# Sheet1.net
KiCad netlist of a schematic drawn in Altium Designer
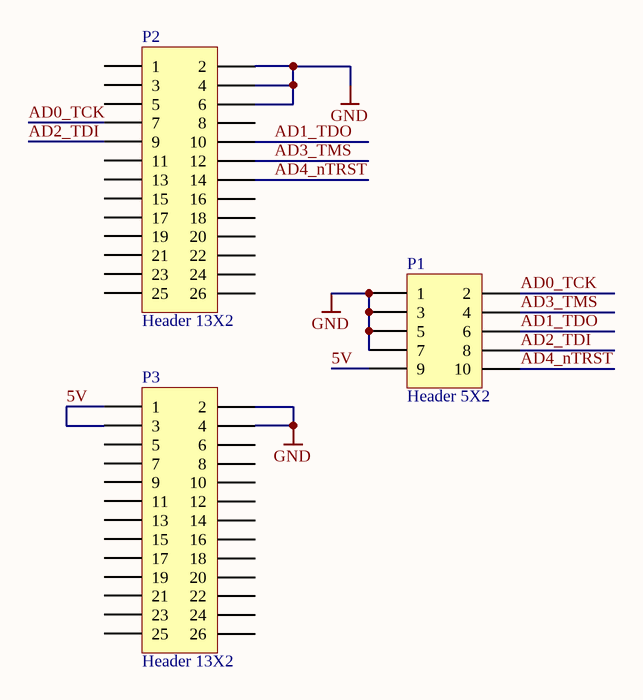
[diagram p0: Sheet1.SchDoc]

(export (version "E")
  (design (tool "Eeschema 10.0.6"))
  (components
    (comp (ref "P1")
      (value "Header 5X2")
      (footprint "HDR2X5")
      (description "Header, 5-Pin, Dual row")
      (fields (field (name "PUBLISHER") "Altium Limited"))
      (libsource (lib "Miscellaneous Connectors") (part "Header 5X2"))
    )
    (comp (ref "P2")
      (value "Header 13X2")
      (footprint "HDR2X13")
      (description "Header, 13-Pin, Dual row")
      (fields (field (name "PUBLISHER") "Altium Limited"))
      (libsource (lib "Miscellaneous Connectors") (part "Header 13X2"))
    )
    (comp (ref "P3")
      (value "Header 13X2")
      (footprint "HDR2X13")
      (description "Header, 13-Pin, Dual row")
      (fields (field (name "PUBLISHER") "Altium Limited"))
      (libsource (lib "Miscellaneous Connectors") (part "Header 13X2"))
    )
  )
  (nets
    (net (code "1") (name "/5V") (class "Default")
      (node (ref "P1") (pin "9") (pinfunction "9_9") (pintype "passive"))
      (node (ref "P3") (pin "1") (pinfunction "1_1") (pintype "passive"))
      (node (ref "P3") (pin "3") (pinfunction "3_3") (pintype "passive"))
    )
    (net (code "2") (name "/AD0_TCK") (class "Default")
      (node (ref "P1") (pin "2") (pinfunction "2_2") (pintype "passive"))
      (node (ref "P2") (pin "7") (pinfunction "7_7") (pintype "passive"))
    )
    (net (code "3") (name "/AD1_TDO") (class "Default")
      (node (ref "P1") (pin "6") (pinfunction "6_6") (pintype "passive"))
      (node (ref "P2") (pin "10") (pinfunction "10_10") (pintype "passive"))
    )
    (net (code "4") (name "/AD2_TDI") (class "Default")
      (node (ref "P1") (pin "8") (pinfunction "8_8") (pintype "passive"))
      (node (ref "P2") (pin "9") (pinfunction "9_9") (pintype "passive"))
    )
    (net (code "5") (name "/AD3_TMS") (class "Default")
      (node (ref "P1") (pin "4") (pinfunction "4_4") (pintype "passive"))
      (node (ref "P2") (pin "12") (pinfunction "12_12") (pintype "passive"))
    )
    (net (code "6") (name "/AD4_nTRST") (class "Default")
      (node (ref "P1") (pin "10") (pinfunction "10_10") (pintype "passive"))
      (node (ref "P2") (pin "14") (pinfunction "14_14") (pintype "passive"))
    )
    (net (code "7") (name "GND") (class "Default")
      (node (ref "P1") (pin "1") (pinfunction "1_1") (pintype "passive"))
      (node (ref "P1") (pin "3") (pinfunction "3_3") (pintype "passive"))
      (node (ref "P1") (pin "5") (pinfunction "5_5") (pintype "passive"))
      (node (ref "P1") (pin "7") (pinfunction "7_7") (pintype "passive"))
      (node (ref "P2") (pin "2") (pinfunction "2_2") (pintype "passive"))
      (node (ref "P2") (pin "4") (pinfunction "4_4") (pintype "passive"))
      (node (ref "P2") (pin "6") (pinfunction "6_6") (pintype "passive"))
      (node (ref "P3") (pin "2") (pinfunction "2_2") (pintype "passive"))
      (node (ref "P3") (pin "4") (pinfunction "4_4") (pintype "passive"))
    )
    (net (code "8") (name "unconnected-(P2-Pad1)") (class "Default")
      (node (ref "P2") (pin "1") (pinfunction "1_1") (pintype "passive"))
    )
    (net (code "9") (name "unconnected-(P2-Pad3)") (class "Default")
      (node (ref "P2") (pin "3") (pinfunction "3_3") (pintype "passive"))
    )
    (net (code "10") (name "unconnected-(P2-Pad5)") (class "Default")
      (node (ref "P2") (pin "5") (pinfunction "5_5") (pintype "passive"))
    )
    (net (code "11") (name "unconnected-(P2-Pad8)") (class "Default")
      (node (ref "P2") (pin "8") (pinfunction "8_8") (pintype "passive"))
    )
    (net (code "12") (name "unconnected-(P2-Pad11)") (class "Default")
      (node (ref "P2") (pin "11") (pinfunction "11_11") (pintype "passive"))
    )
    (net (code "13") (name "unconnected-(P2-Pad13)") (class "Default")
      (node (ref "P2") (pin "13") (pinfunction "13_13") (pintype "passive"))
    )
    (net (code "14") (name "unconnected-(P2-Pad15)") (class "Default")
      (node (ref "P2") (pin "15") (pinfunction "15_15") (pintype "passive"))
    )
    (net (code "15") (name "unconnected-(P2-Pad16)") (class "Default")
      (node (ref "P2") (pin "16") (pinfunction "16_16") (pintype "passive"))
    )
    (net (code "16") (name "unconnected-(P2-Pad17)") (class "Default")
      (node (ref "P2") (pin "17") (pinfunction "17_17") (pintype "passive"))
    )
    (net (code "17") (name "unconnected-(P2-Pad18)") (class "Default")
      (node (ref "P2") (pin "18") (pinfunction "18_18") (pintype "passive"))
    )
    (net (code "18") (name "unconnected-(P2-Pad19)") (class "Default")
      (node (ref "P2") (pin "19") (pinfunction "19_19") (pintype "passive"))
    )
    (net (code "19") (name "unconnected-(P2-Pad20)") (class "Default")
      (node (ref "P2") (pin "20") (pinfunction "20_20") (pintype "passive"))
    )
    (net (code "20") (name "unconnected-(P2-Pad21)") (class "Default")
      (node (ref "P2") (pin "21") (pinfunction "21_21") (pintype "passive"))
    )
    (net (code "21") (name "unconnected-(P2-Pad22)") (class "Default")
      (node (ref "P2") (pin "22") (pinfunction "22_22") (pintype "passive"))
    )
    (net (code "22") (name "unconnected-(P2-Pad23)") (class "Default")
      (node (ref "P2") (pin "23") (pinfunction "23_23") (pintype "passive"))
    )
    (net (code "23") (name "unconnected-(P2-Pad24)") (class "Default")
      (node (ref "P2") (pin "24") (pinfunction "24_24") (pintype "passive"))
    )
    (net (code "24") (name "unconnected-(P2-Pad25)") (class "Default")
      (node (ref "P2") (pin "25") (pinfunction "25_25") (pintype "passive"))
    )
    (net (code "25") (name "unconnected-(P2-Pad26)") (class "Default")
      (node (ref "P2") (pin "26") (pinfunction "26_26") (pintype "passive"))
    )
    (net (code "26") (name "unconnected-(P3-Pad5)") (class "Default")
      (node (ref "P3") (pin "5") (pinfunction "5_5") (pintype "passive"))
    )
    (net (code "27") (name "unconnected-(P3-Pad6)") (class "Default")
      (node (ref "P3") (pin "6") (pinfunction "6_6") (pintype "passive"))
    )
    (net (code "28") (name "unconnected-(P3-Pad7)") (class "Default")
      (node (ref "P3") (pin "7") (pinfunction "7_7") (pintype "passive"))
    )
    (net (code "29") (name "unconnected-(P3-Pad8)") (class "Default")
      (node (ref "P3") (pin "8") (pinfunction "8_8") (pintype "passive"))
    )
    (net (code "30") (name "unconnected-(P3-Pad9)") (class "Default")
      (node (ref "P3") (pin "9") (pinfunction "9_9") (pintype "passive"))
    )
    (net (code "31") (name "unconnected-(P3-Pad10)") (class "Default")
      (node (ref "P3") (pin "10") (pinfunction "10_10") (pintype "passive"))
    )
    (net (code "32") (name "unconnected-(P3-Pad11)") (class "Default")
      (node (ref "P3") (pin "11") (pinfunction "11_11") (pintype "passive"))
    )
    (net (code "33") (name "unconnected-(P3-Pad12)") (class "Default")
      (node (ref "P3") (pin "12") (pinfunction "12_12") (pintype "passive"))
    )
    (net (code "34") (name "unconnected-(P3-Pad13)") (class "Default")
      (node (ref "P3") (pin "13") (pinfunction "13_13") (pintype "passive"))
    )
    (net (code "35") (name "unconnected-(P3-Pad14)") (class "Default")
      (node (ref "P3") (pin "14") (pinfunction "14_14") (pintype "passive"))
    )
    (net (code "36") (name "unconnected-(P3-Pad15)") (class "Default")
      (node (ref "P3") (pin "15") (pinfunction "15_15") (pintype "passive"))
    )
    (net (code "37") (name "unconnected-(P3-Pad16)") (class "Default")
      (node (ref "P3") (pin "16") (pinfunction "16_16") (pintype "passive"))
    )
    (net (code "38") (name "unconnected-(P3-Pad17)") (class "Default")
      (node (ref "P3") (pin "17") (pinfunction "17_17") (pintype "passive"))
    )
    (net (code "39") (name "unconnected-(P3-Pad18)") (class "Default")
      (node (ref "P3") (pin "18") (pinfunction "18_18") (pintype "passive"))
    )
    (net (code "40") (name "unconnected-(P3-Pad19)") (class "Default")
      (node (ref "P3") (pin "19") (pinfunction "19_19") (pintype "passive"))
    )
    (net (code "41") (name "unconnected-(P3-Pad20)") (class "Default")
      (node (ref "P3") (pin "20") (pinfunction "20_20") (pintype "passive"))
    )
    (net (code "42") (name "unconnected-(P3-Pad21)") (class "Default")
      (node (ref "P3") (pin "21") (pinfunction "21_21") (pintype "passive"))
    )
    (net (code "43") (name "unconnected-(P3-Pad22)") (class "Default")
      (node (ref "P3") (pin "22") (pinfunction "22_22") (pintype "passive"))
    )
    (net (code "44") (name "unconnected-(P3-Pad23)") (class "Default")
      (node (ref "P3") (pin "23") (pinfunction "23_23") (pintype "passive"))
    )
    (net (code "45") (name "unconnected-(P3-Pad24)") (class "Default")
      (node (ref "P3") (pin "24") (pinfunction "24_24") (pintype "passive"))
    )
    (net (code "46") (name "unconnected-(P3-Pad25)") (class "Default")
      (node (ref "P3") (pin "25") (pinfunction "25_25") (pintype "passive"))
    )
    (net (code "47") (name "unconnected-(P3-Pad26)") (class "Default")
      (node (ref "P3") (pin "26") (pinfunction "26_26") (pintype "passive"))
    )
  )
)
